# LED.net
KiCad netlist of a schematic drawn in Altium Designer
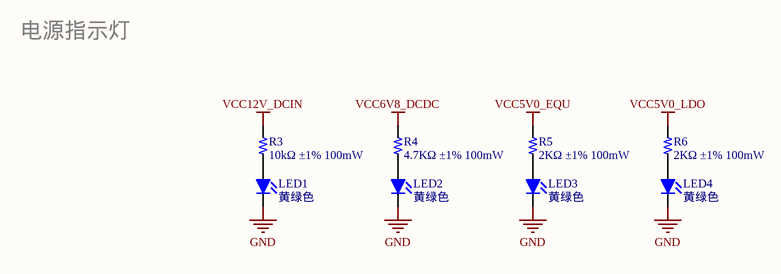
[diagram p0: LED.SchDoc]

(export (version "E")
  (design (tool "Eeschema 10.0.6"))
  (components
    (comp (ref "LED1") (value "黄绿色") (footprint "LED-0805") (libsource (lib "Device") (part "LED-0805")))
    (comp (ref "LED2") (value "黄绿色") (footprint "LED-0805") (libsource (lib "Device") (part "LED-0805")))
    (comp (ref "LED3") (value "黄绿色") (footprint "LED-0805") (libsource (lib "Device") (part "LED-0805")))
    (comp (ref "LED4") (value "黄绿色") (footprint "LED-0805") (libsource (lib "Device") (part "LED-0805")))
    (comp (ref "R3")
      (value "10kΩ ±1% 100mW")
      (footprint "R-0603")
      (description "国巨RC0805FR-0710K")
      (libsource (lib "电阻") (part "10K_1"))
    )
    (comp (ref "R4")
      (value "4.7KΩ ±1% 100mW")
      (footprint "R-0603")
      (description "国巨RC0805FR-0710K")
      (libsource (lib "电阻") (part "10K_1"))
    )
    (comp (ref "R5")
      (value "2KΩ ±1% 100mW")
      (footprint "R-0603")
      (description "国巨RC0805FR-0710K")
      (libsource (lib "电阻") (part "10K_1"))
    )
    (comp (ref "R6")
      (value "2KΩ ±1% 100mW")
      (footprint "R-0603")
      (description "国巨RC0805FR-0710K")
      (libsource (lib "电阻") (part "10K_1"))
    )
  )
  (nets
    (net (code "1") (name "GND") (class "Default")
      (node (ref "LED1") (pin "K") (pinfunction "K_K") (pintype "passive"))
      (node (ref "LED2") (pin "K") (pinfunction "K_K") (pintype "passive"))
      (node (ref "LED3") (pin "K") (pinfunction "K_K") (pintype "passive"))
      (node (ref "LED4") (pin "K") (pinfunction "K_K") (pintype "passive"))
    )
    (net (code "2") (name "Net-(R3-TOP)") (class "Default")
      (node (ref "LED1") (pin "A") (pinfunction "A_A") (pintype "passive"))
      (node (ref "R3") (pin "1") (pinfunction "TOP_1") (pintype "passive"))
    )
    (net (code "3") (name "Net-(R4-TOP)") (class "Default")
      (node (ref "LED2") (pin "A") (pinfunction "A_A") (pintype "passive"))
      (node (ref "R4") (pin "1") (pinfunction "TOP_1") (pintype "passive"))
    )
    (net (code "4") (name "Net-(R5-TOP)") (class "Default")
      (node (ref "LED3") (pin "A") (pinfunction "A_A") (pintype "passive"))
      (node (ref "R5") (pin "1") (pinfunction "TOP_1") (pintype "passive"))
    )
    (net (code "5") (name "Net-(R6-TOP)") (class "Default")
      (node (ref "LED4") (pin "A") (pinfunction "A_A") (pintype "passive"))
      (node (ref "R6") (pin "1") (pinfunction "TOP_1") (pintype "passive"))
    )
    (net (code "6") (name "VCC5V0_EQU") (class "Default")
      (node (ref "R5") (pin "2") (pinfunction "BOT_2") (pintype "passive"))
    )
    (net (code "7") (name "VCC5V0_LDO") (class "Default")
      (node (ref "R6") (pin "2") (pinfunction "BOT_2") (pintype "passive"))
    )
    (net (code "8") (name "VCC6V8_DCDC") (class "Default")
      (node (ref "R4") (pin "2") (pinfunction "BOT_2") (pintype "passive"))
    )
    (net (code "9") (name "VCC12V_DCIN") (class "Default")
      (node (ref "R3") (pin "2") (pinfunction "BOT_2") (pintype "passive"))
    )
  )
)
